# Power.net
KiCad netlist of a schematic drawn in Altium Designer
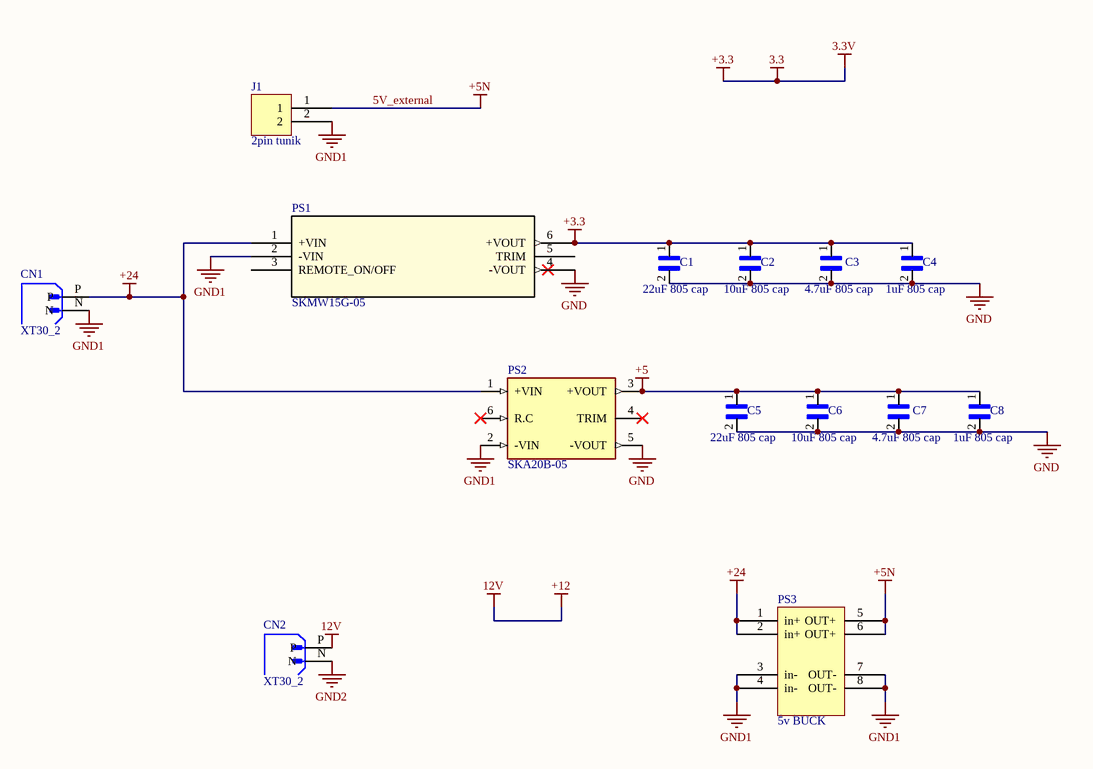
[diagram p0: Power.SchDoc]

(export (version "E")
  (design (tool "Eeschema 10.0.6"))
  (components
    (comp (ref "C1")
      (value "22uF 805 cap")
      (footprint "1uF 805 Cap")
      (libsource (lib "iee_altium") (part "1uF 805 cap"))
    )
    (comp (ref "C2")
      (value "10uF 805 cap")
      (footprint "1uF 805 Cap")
      (libsource (lib "iee_altium") (part "1uF 805 cap"))
    )
    (comp (ref "C3")
      (value "4.7uF 805 cap")
      (footprint "1uF 805 Cap")
      (libsource (lib "iee_altium") (part "1uF 805 cap"))
    )
    (comp (ref "C4")
      (value "1uF 805 cap")
      (footprint "1uF 805 Cap")
      (libsource (lib "iee_altium") (part "1uF 805 cap"))
    )
    (comp (ref "C5")
      (value "22uF 805 cap")
      (footprint "1uF 805 Cap")
      (libsource (lib "iee_altium") (part "1uF 805 cap"))
    )
    (comp (ref "C6")
      (value "10uF 805 cap")
      (footprint "1uF 805 Cap")
      (libsource (lib "iee_altium") (part "1uF 805 cap"))
    )
    (comp (ref "C7")
      (value "4.7uF 805 cap")
      (footprint "1uF 805 Cap")
      (libsource (lib "iee_altium") (part "1uF 805 cap"))
    )
    (comp (ref "C8")
      (value "1uF 805 cap")
      (footprint "1uF 805 Cap")
      (libsource (lib "iee_altium") (part "1uF 805 cap"))
    )
    (comp (ref "CN1") (value "XT30_2") (footprint "XT30_2") (libsource (lib "iee_altium") (part "XT30_2")))
    (comp (ref "CN2") (value "XT30_2") (footprint "XT30_2") (libsource (lib "iee_altium") (part "XT30_2")))
    (comp (ref "J1")
      (value "2pin tunik")
      (footprint "2pin tunşk")
      (libsource (lib "iee_altium") (part "2pin tunik"))
    )
    (comp (ref "PS1")
      (value "SKMW15G-05")
      (footprint "SKMW15DKMW15_MWU")
      (description "No Description Available")
      (fields (field (name "COPYRIGHT") "Copyright (C) 2025 Ultra Librarian. All rights reserved."))
      (libsource (lib "iee_altium") (part "SKMW15G-03_1"))
    )
    (comp (ref "PS2")
      (value "SKA20B-05")
      (footprint "CONV_SKA20B-05")
      (description "Isolated Module DC DC Converter 1 Output 5V 4A 18V - 36V Input")
      (libsource (lib "iee_altium") (part "SKA20B-05"))
    )
    (comp (ref "PS3")
      (value "5v BUCK")
      (footprint "5V Buck Conv")
      (libsource (lib "iee_altium") (part "5v BUCK"))
    )
  )
  (nets
    (net (code "1") (name "+3.3") (class "Default")
      (node (ref "C1") (pin "1") (pinfunction "1_1") (pintype "passive"))
      (node (ref "C2") (pin "1") (pinfunction "1_1") (pintype "passive"))
      (node (ref "C3") (pin "1") (pinfunction "1_1") (pintype "passive"))
      (node (ref "C4") (pin "1") (pinfunction "1_1") (pintype "passive"))
      (node (ref "PS1") (pin "6") (pinfunction "+VOUT_6") (pintype "output"))
    )
    (net (code "2") (name "+5") (class "Default")
      (node (ref "C5") (pin "1") (pinfunction "1_1") (pintype "passive"))
      (node (ref "C6") (pin "1") (pinfunction "1_1") (pintype "passive"))
      (node (ref "C7") (pin "1") (pinfunction "1_1") (pintype "passive"))
      (node (ref "C8") (pin "1") (pinfunction "1_1") (pintype "passive"))
      (node (ref "PS2") (pin "3") (pinfunction "+VOUT_3") (pintype "output"))
    )
    (net (code "3") (name "+5N") (class "Default")
      (node (ref "J1") (pin "1") (pinfunction "1_1") (pintype "passive"))
      (node (ref "PS3") (pin "5") (pinfunction "OUT+_5") (pintype "passive"))
      (node (ref "PS3") (pin "6") (pinfunction "OUT+_6") (pintype "passive"))
    )
    (net (code "4") (name "+12") (class "Default")
      (node (ref "CN2") (pin "P") (pinfunction "P_P") (pintype "power_in"))
    )
    (net (code "5") (name "+24") (class "Default")
      (node (ref "CN1") (pin "P") (pinfunction "P_P") (pintype "power_in"))
      (node (ref "PS1") (pin "1") (pinfunction "+VIN_1") (pintype "power_in"))
      (node (ref "PS2") (pin "1") (pinfunction "+VIN_1") (pintype "input"))
      (node (ref "PS3") (pin "1") (pinfunction "in+_1") (pintype "passive"))
      (node (ref "PS3") (pin "2") (pinfunction "in+_2") (pintype "passive"))
    )
    (net (code "6") (name "GND") (class "Default")
      (node (ref "C1") (pin "2") (pinfunction "2_2") (pintype "passive"))
      (node (ref "C2") (pin "2") (pinfunction "2_2") (pintype "passive"))
      (node (ref "C3") (pin "2") (pinfunction "2_2") (pintype "passive"))
      (node (ref "C4") (pin "2") (pinfunction "2_2") (pintype "passive"))
      (node (ref "C5") (pin "2") (pinfunction "2_2") (pintype "passive"))
      (node (ref "C6") (pin "2") (pinfunction "2_2") (pintype "passive"))
      (node (ref "C7") (pin "2") (pinfunction "2_2") (pintype "passive"))
      (node (ref "C8") (pin "2") (pinfunction "2_2") (pintype "passive"))
      (node (ref "PS1") (pin "4") (pinfunction "-VOUT_4") (pintype "output"))
      (node (ref "PS2") (pin "5") (pinfunction "-VOUT_5") (pintype "output"))
    )
    (net (code "7") (name "GND1") (class "Default")
      (node (ref "CN1") (pin "N") (pinfunction "N_N") (pintype "power_in"))
      (node (ref "J1") (pin "2") (pinfunction "2_2") (pintype "passive"))
      (node (ref "PS1") (pin "2") (pinfunction "-VIN_2") (pintype "power_in"))
      (node (ref "PS2") (pin "2") (pinfunction "-VIN_2") (pintype "input"))
      (node (ref "PS3") (pin "3") (pinfunction "in-_3") (pintype "passive"))
      (node (ref "PS3") (pin "4") (pinfunction "in-_4") (pintype "passive"))
      (node (ref "PS3") (pin "7") (pinfunction "OUT-_7") (pintype "passive"))
      (node (ref "PS3") (pin "8") (pinfunction "OUT-_8") (pintype "passive"))
    )
    (net (code "8") (name "GND2") (class "Default")
      (node (ref "CN2") (pin "N") (pinfunction "N_N") (pintype "power_in"))
    )
    (net (code "9") (name "unconnected-(PS1-REMOTE_ON{slash}OFF-Pad3)") (class "Default")
      (node (ref "PS1") (pin "3") (pinfunction "REMOTE_ON/OFF_3") (pintype "passive"))
    )
    (net (code "10") (name "unconnected-(PS1-TRIM-Pad5)") (class "Default")
      (node (ref "PS1") (pin "5") (pinfunction "TRIM_5") (pintype "passive"))
    )
    (net (code "11") (name "unconnected-(PS2-R.C-Pad6)") (class "Default")
      (node (ref "PS2") (pin "6") (pinfunction "R.C_6") (pintype "input+no_connect"))
    )
    (net (code "12") (name "unconnected-(PS2-TRIM-Pad4)") (class "Default")
      (node (ref "PS2") (pin "4") (pinfunction "TRIM_4") (pintype "passive+no_connect"))
    )
  )
)
